# MSP430.net
KiCad netlist of a schematic drawn in Altium Designer
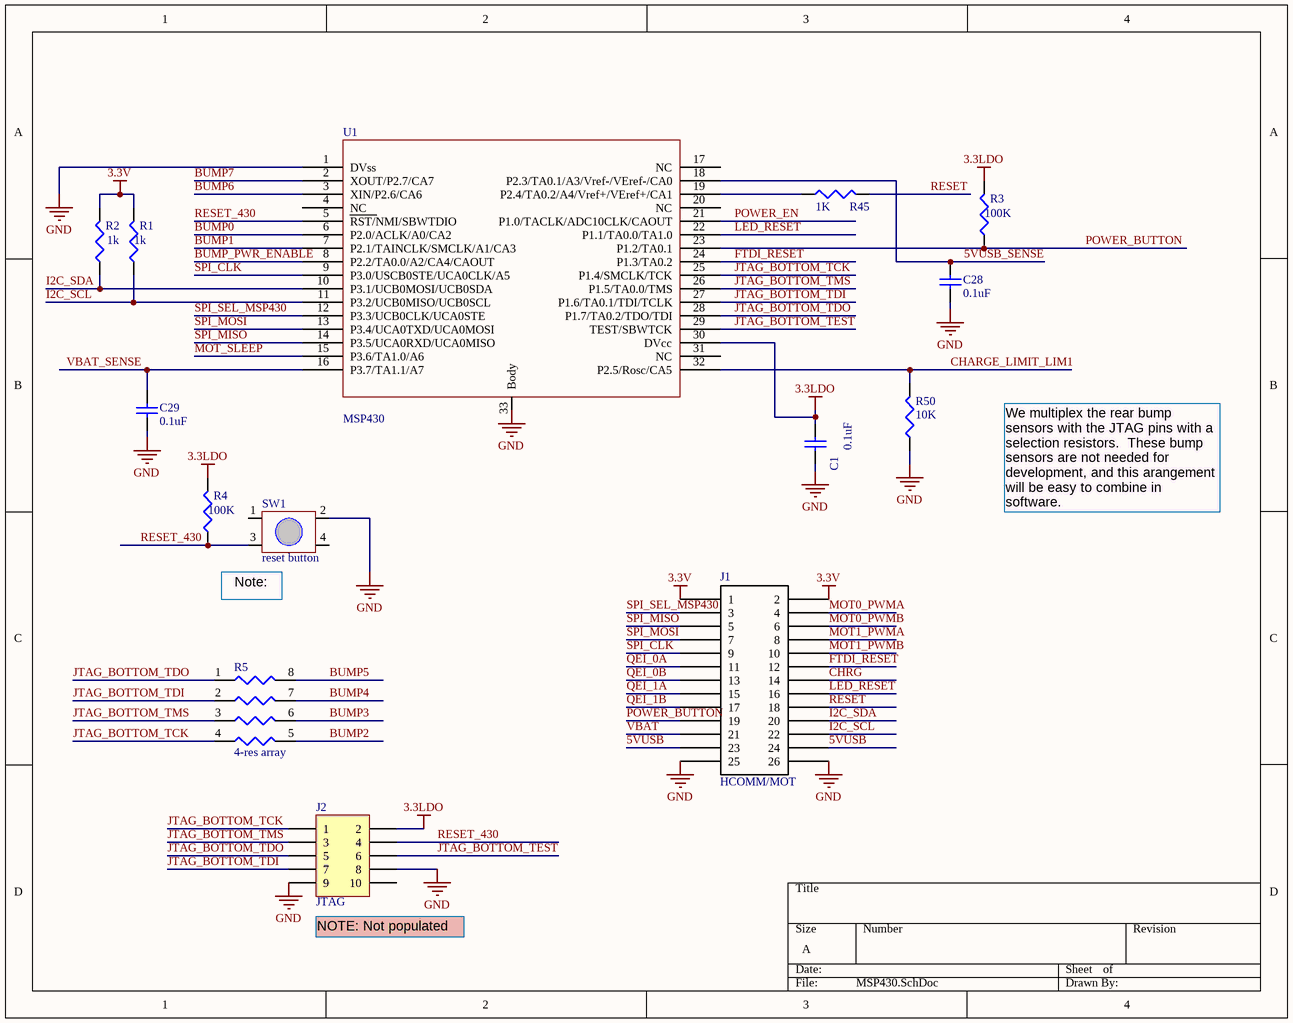
[diagram p0: MSP430.SchDoc]

(export (version "E")
  (design (tool "Eeschema 10.0.6"))
  (components
    (comp (ref "C1")
      (value "0.1uF")
      (footprint "CAPC1005L")
      (description "Capacitor (Semiconductor SIM Model)")
      (fields (field (name "Comment") "Cap Semi") (field (name "PUBLISHER") "Altium Limited"))
      (libsource (lib "Miscellaneous Devices") (part "Cap Semi"))
    )
    (comp (ref "C28")
      (value "0.1uF")
      (footprint "CAPC1005L")
      (description "Capacitor (Semiconductor SIM Model)")
      (fields (field (name "Comment") "Cap Semi") (field (name "PUBLISHER") "Altium Limited"))
      (libsource (lib "Miscellaneous Devices") (part "Cap Semi"))
    )
    (comp (ref "C29")
      (value "0.1uF")
      (footprint "CAPC1005L")
      (description "Capacitor (Semiconductor SIM Model)")
      (fields (field (name "Comment") "Cap Semi") (field (name "PUBLISHER") "Altium Limited"))
      (libsource (lib "Miscellaneous Devices") (part "Cap Semi"))
    )
    (comp (ref "J1")
      (value "HCOMM/MOT")
      (footprint "HeaderSM 13x2")
      (description "Header, 2X20, 50mil, IDC")
      (libsource (lib "mrone") (part "HCOMM/HMOT"))
    )
    (comp (ref "J2")
      (value "JTAG")
      (footprint "HDR2X5")
      (description "Header, 5-Pin, Dual row")
      (fields (field (name "PUBLISHER") "Altium Limited"))
      (libsource (lib "Miscellaneous Connectors") (part "Header 5X2"))
    )
    (comp (ref "R1")
      (value "1k")
      (footprint "RESC1608L")
      (description "Resistor")
      (fields (field (name "Comment") "Res3") (field (name "PUBLISHER") "Altium Limited"))
      (libsource (lib "Miscellaneous Devices") (part "Res3"))
    )
    (comp (ref "R2")
      (value "1k")
      (footprint "RESC1608L")
      (description "Resistor")
      (fields (field (name "Comment") "Res3") (field (name "PUBLISHER") "Altium Limited"))
      (libsource (lib "Miscellaneous Devices") (part "Res3"))
    )
    (comp (ref "R3")
      (value "100K")
      (footprint "RESC1608L")
      (description "Resistor")
      (fields (field (name "Comment") "Res3") (field (name "PUBLISHER") "Altium Limited"))
      (libsource (lib "Miscellaneous Devices") (part "Res3"))
    )
    (comp (ref "R4")
      (value "100K")
      (footprint "RESC1608L")
      (description "Resistor")
      (fields (field (name "Comment") "Res3") (field (name "PUBLISHER") "Altium Limited"))
      (libsource (lib "Miscellaneous Devices") (part "Res3"))
    )
    (comp (ref "R5")
      (value "4-res array")
      (footprint "4-RES ARRAY")
      (libsource (lib "mrone") (part "4 Res Array"))
    )
    (comp (ref "R45")
      (value "1K")
      (footprint "J1-0603")
      (description "Resistor")
      (fields (field (name "PUBLISHER") "Altium Limited"))
      (libsource (lib "Miscellaneous Devices") (part "Res3"))
    )
    (comp (ref "R50")
      (value "10K")
      (footprint "RESC1608L")
      (description "Resistor")
      (fields (field (name "Comment") "Res3") (field (name "PUBLISHER") "Altium Limited"))
      (libsource (lib "Miscellaneous Devices") (part "Res3"))
    )
    (comp (ref "SW1")
      (value "reset button")
      (footprint "SwitchTall-TL330")
      (libsource (lib "mrone") (part "Switch-TL330"))
    )
    (comp (ref "U1")
      (value "MSP430")
      (footprint "MSP430_32PIN")
      (libsource (lib "mrone") (part "MSP430_32pin"))
    )
  )
  (nets
    (net (code "1") (name "/5VUSB") (class "Default")
      (node (ref "J1") (pin "23") (pinfunction "23_23") (pintype "passive"))
      (node (ref "J1") (pin "24") (pinfunction "24_24") (pintype "passive"))
    )
    (net (code "2") (name "/5VUSB_SENSE") (class "Default")
      (node (ref "C28") (pin "2") (pinfunction "2_2") (pintype "passive"))
      (node (ref "U1") (pin "18") (pinfunction "P2.3/TA0.1/A3/Vref-/VEref-/CA0_18") (pintype "passive"))
    )
    (net (code "3") (name "/BUMP0") (class "Default")
      (node (ref "U1") (pin "6") (pinfunction "P2.0/ACLK/A0/CA2_6") (pintype "passive"))
    )
    (net (code "4") (name "/BUMP1") (class "Default")
      (node (ref "U1") (pin "7") (pinfunction "P2.1/TAINCLK/SMCLK/A1/CA3_7") (pintype "passive"))
    )
    (net (code "5") (name "/BUMP2") (class "Default")
      (node (ref "R5") (pin "5") (pinfunction "5_5") (pintype "passive"))
    )
    (net (code "6") (name "/BUMP3") (class "Default")
      (node (ref "R5") (pin "6") (pinfunction "6_6") (pintype "passive"))
    )
    (net (code "7") (name "/BUMP4") (class "Default")
      (node (ref "R5") (pin "7") (pinfunction "7_7") (pintype "passive"))
    )
    (net (code "8") (name "/BUMP5") (class "Default")
      (node (ref "R5") (pin "8") (pinfunction "8_8") (pintype "passive"))
    )
    (net (code "9") (name "/BUMP6") (class "Default")
      (node (ref "U1") (pin "3") (pinfunction "XIN/P2.6/CA6_3") (pintype "passive"))
    )
    (net (code "10") (name "/BUMP7") (class "Default")
      (node (ref "U1") (pin "2") (pinfunction "XOUT/P2.7/CA7_2") (pintype "passive"))
    )
    (net (code "11") (name "/BUMP_PWR_ENABLE") (class "Default")
      (node (ref "U1") (pin "8") (pinfunction "P2.2/TA0.0/A2/CA4/CAOUT_8") (pintype "passive"))
    )
    (net (code "12") (name "/CHARGE_LIMIT_LIM1") (class "Default")
      (node (ref "R50") (pin "2") (pinfunction "2_2") (pintype "passive"))
      (node (ref "U1") (pin "32") (pinfunction "P2.5/Rosc/CA5_32") (pintype "passive"))
    )
    (net (code "13") (name "/CHRG") (class "Default")
      (node (ref "J1") (pin "14") (pinfunction "14_14") (pintype "passive"))
    )
    (net (code "14") (name "/FTDI_RESET") (class "Default")
      (node (ref "J1") (pin "12") (pinfunction "12_12") (pintype "passive"))
      (node (ref "U1") (pin "24") (pinfunction "P1.3/TA0.2_24") (pintype "passive"))
    )
    (net (code "15") (name "/I2C_SCL") (class "Default")
      (node (ref "J1") (pin "22") (pinfunction "22_22") (pintype "passive"))
      (node (ref "R1") (pin "1") (pinfunction "1_1") (pintype "passive"))
      (node (ref "U1") (pin "11") (pinfunction "P3.2/UCB0MISO/UCB0SCL_11") (pintype "passive"))
    )
    (net (code "16") (name "/I2C_SDA") (class "Default")
      (node (ref "J1") (pin "20") (pinfunction "20_20") (pintype "passive"))
      (node (ref "R2") (pin "1") (pinfunction "1_1") (pintype "passive"))
      (node (ref "U1") (pin "10") (pinfunction "P3.1/UCB0MOSI/UCB0SDA_10") (pintype "passive"))
    )
    (net (code "17") (name "/JTAG_BOTTOM_TCK") (class "Default")
      (node (ref "J2") (pin "1") (pinfunction "1_1") (pintype "passive"))
      (node (ref "R5") (pin "4") (pinfunction "4_4") (pintype "passive"))
      (node (ref "U1") (pin "25") (pinfunction "P1.4/SMCLK/TCK_25") (pintype "passive"))
    )
    (net (code "18") (name "/JTAG_BOTTOM_TDI") (class "Default")
      (node (ref "J2") (pin "7") (pinfunction "7_7") (pintype "passive"))
      (node (ref "R5") (pin "2") (pinfunction "2_2") (pintype "passive"))
      (node (ref "U1") (pin "27") (pinfunction "P1.6/TA0.1/TDI/TCLK_27") (pintype "passive"))
    )
    (net (code "19") (name "/JTAG_BOTTOM_TDO") (class "Default")
      (node (ref "J2") (pin "5") (pinfunction "5_5") (pintype "passive"))
      (node (ref "R5") (pin "1") (pinfunction "1_1") (pintype "passive"))
      (node (ref "U1") (pin "28") (pinfunction "P1.7/TA0.2/TDO/TDI_28") (pintype "passive"))
    )
    (net (code "20") (name "/JTAG_BOTTOM_TEST") (class "Default")
      (node (ref "J2") (pin "6") (pinfunction "6_6") (pintype "passive"))
      (node (ref "U1") (pin "29") (pinfunction "TEST/SBWTCK_29") (pintype "passive"))
    )
    (net (code "21") (name "/JTAG_BOTTOM_TMS") (class "Default")
      (node (ref "J2") (pin "3") (pinfunction "3_3") (pintype "passive"))
      (node (ref "R5") (pin "3") (pinfunction "3_3") (pintype "passive"))
      (node (ref "U1") (pin "26") (pinfunction "P1.5/TA0.0/TMS_26") (pintype "passive"))
    )
    (net (code "22") (name "/LED_RESET") (class "Default")
      (node (ref "J1") (pin "16") (pinfunction "16_16") (pintype "passive"))
      (node (ref "U1") (pin "22") (pinfunction "P1.1/TA0.0/TA1.0_22") (pintype "passive"))
    )
    (net (code "23") (name "/MOT0_PWMA") (class "Default")
      (node (ref "J1") (pin "4") (pinfunction "4_4") (pintype "passive"))
    )
    (net (code "24") (name "/MOT0_PWMB") (class "Default")
      (node (ref "J1") (pin "6") (pinfunction "6_6") (pintype "passive"))
    )
    (net (code "25") (name "/MOT1_PWMA") (class "Default")
      (node (ref "J1") (pin "8") (pinfunction "8_8") (pintype "passive"))
    )
    (net (code "26") (name "/MOT1_PWMB") (class "Default")
      (node (ref "J1") (pin "10") (pinfunction "10_10") (pintype "passive"))
    )
    (net (code "27") (name "/MOT_SLEEP") (class "Default")
      (node (ref "U1") (pin "15") (pinfunction "P3.6/TA1.0/A6_15") (pintype "passive"))
    )
    (net (code "28") (name "/POWER_BUTTON") (class "Default")
      (node (ref "J1") (pin "19") (pinfunction "19_19") (pintype "passive"))
      (node (ref "R3") (pin "1") (pinfunction "1_1") (pintype "passive"))
      (node (ref "U1") (pin "23") (pinfunction "P1.2/TA0.1_23") (pintype "passive"))
    )
    (net (code "29") (name "/POWER_EN") (class "Default")
      (node (ref "U1") (pin "21") (pinfunction "P1.0/TACLK/ADC10CLK/CAOUT_21") (pintype "passive"))
    )
    (net (code "30") (name "/QEI_0A") (class "Default")
      (node (ref "J1") (pin "11") (pinfunction "11_11") (pintype "passive"))
    )
    (net (code "31") (name "/QEI_0B") (class "Default")
      (node (ref "J1") (pin "13") (pinfunction "13_13") (pintype "passive"))
    )
    (net (code "32") (name "/QEI_1A") (class "Default")
      (node (ref "J1") (pin "15") (pinfunction "15_15") (pintype "passive"))
    )
    (net (code "33") (name "/QEI_1B") (class "Default")
      (node (ref "J1") (pin "17") (pinfunction "17_17") (pintype "passive"))
    )
    (net (code "34") (name "/RESET") (class "Default")
      (node (ref "J1") (pin "18") (pinfunction "18_18") (pintype "passive"))
      (node (ref "R45") (pin "2") (pinfunction "2_2") (pintype "passive"))
    )
    (net (code "35") (name "/RESET_430") (class "Default")
      (node (ref "J2") (pin "4") (pinfunction "4_4") (pintype "passive"))
      (node (ref "R4") (pin "1") (pinfunction "1_1") (pintype "passive"))
      (node (ref "SW1") (pin "3") (pinfunction "3_3") (pintype "passive"))
      (node (ref "U1") (pin "5") (pinfunction "RST/NMI/SBWTDIO_5") (pintype "passive"))
    )
    (net (code "36") (name "/SPI_CLK") (class "Default")
      (node (ref "J1") (pin "9") (pinfunction "9_9") (pintype "passive"))
      (node (ref "U1") (pin "9") (pinfunction "P3.0/USCB0STE/UCA0CLK/A5_9") (pintype "passive"))
    )
    (net (code "37") (name "/SPI_MISO") (class "Default")
      (node (ref "J1") (pin "5") (pinfunction "5_5") (pintype "passive"))
      (node (ref "U1") (pin "14") (pinfunction "P3.5/UCA0RXD/UCA0MISO_14") (pintype "passive"))
    )
    (net (code "38") (name "/SPI_MOSI") (class "Default")
      (node (ref "J1") (pin "7") (pinfunction "7_7") (pintype "passive"))
      (node (ref "U1") (pin "13") (pinfunction "P3.4/UCA0TXD/UCA0MOSI_13") (pintype "passive"))
    )
    (net (code "39") (name "/SPI_SEL_MSP430") (class "Default")
      (node (ref "J1") (pin "3") (pinfunction "3_3") (pintype "passive"))
      (node (ref "U1") (pin "12") (pinfunction "P3.3/UCB0CLK/UCA0STE_12") (pintype "passive"))
    )
    (net (code "40") (name "/VBAT") (class "Default")
      (node (ref "J1") (pin "21") (pinfunction "21_21") (pintype "passive"))
    )
    (net (code "41") (name "/VBAT_SENSE") (class "Default")
      (node (ref "C29") (pin "2") (pinfunction "2_2") (pintype "passive"))
      (node (ref "U1") (pin "16") (pinfunction "P3.7/TA1.1/A7_16") (pintype "passive"))
    )
    (net (code "42") (name "3.3LDO") (class "Default")
      (node (ref "C1") (pin "2") (pinfunction "2_2") (pintype "passive"))
      (node (ref "J2") (pin "2") (pinfunction "2_2") (pintype "passive"))
      (node (ref "R3") (pin "2") (pinfunction "2_2") (pintype "passive"))
      (node (ref "R4") (pin "2") (pinfunction "2_2") (pintype "passive"))
      (node (ref "U1") (pin "30") (pinfunction "DVcc_30") (pintype "passive"))
    )
    (net (code "43") (name "3.3V") (class "Default")
      (node (ref "J1") (pin "1") (pinfunction "1_1") (pintype "passive"))
      (node (ref "J1") (pin "2") (pinfunction "2_2") (pintype "passive"))
      (node (ref "R1") (pin "2") (pinfunction "2_2") (pintype "passive"))
      (node (ref "R2") (pin "2") (pinfunction "2_2") (pintype "passive"))
    )
    (net (code "44") (name "GND") (class "Default")
      (node (ref "C1") (pin "1") (pinfunction "1_1") (pintype "passive"))
      (node (ref "C28") (pin "1") (pinfunction "1_1") (pintype "passive"))
      (node (ref "C29") (pin "1") (pinfunction "1_1") (pintype "passive"))
      (node (ref "J1") (pin "25") (pinfunction "25_25") (pintype "passive"))
      (node (ref "J1") (pin "26") (pinfunction "26_26") (pintype "passive"))
      (node (ref "J2") (pin "8") (pinfunction "8_8") (pintype "passive"))
      (node (ref "J2") (pin "9") (pinfunction "9_9") (pintype "passive"))
      (node (ref "R50") (pin "1") (pinfunction "1_1") (pintype "passive"))
      (node (ref "SW1") (pin "2") (pinfunction "2_2") (pintype "passive"))
      (node (ref "U1") (pin "1") (pinfunction "DVss_1") (pintype "passive"))
      (node (ref "U1") (pin "33") (pinfunction "Body_33") (pintype "power_in"))
    )
    (net (code "45") (name "Net-(U1-P2.4{slash}TA0.2{slash}A4{slash}Vref+{slash}VEref+{slash}CA1)") (class "Default")
      (node (ref "R45") (pin "1") (pinfunction "1_1") (pintype "passive"))
      (node (ref "U1") (pin "19") (pinfunction "P2.4/TA0.2/A4/Vref+/VEref+/CA1_19") (pintype "passive"))
    )
    (net (code "46") (name "unconnected-(J2-Pad10)") (class "Default")
      (node (ref "J2") (pin "10") (pinfunction "10_10") (pintype "passive"))
    )
    (net (code "47") (name "unconnected-(SW1-Pad1)") (class "Default")
      (node (ref "SW1") (pin "1") (pinfunction "1_1") (pintype "passive"))
    )
    (net (code "48") (name "unconnected-(SW1-Pad4)") (class "Default")
      (node (ref "SW1") (pin "4") (pinfunction "4_4") (pintype "passive"))
    )
    (net (code "49") (name "unconnected-(U1-NC-Pad4)") (class "Default")
      (node (ref "U1") (pin "4") (pinfunction "NC_4") (pintype "passive"))
    )
    (net (code "50") (name "unconnected-(U1-NC-Pad17)") (class "Default")
      (node (ref "U1") (pin "17") (pinfunction "NC_17") (pintype "passive"))
    )
    (net (code "51") (name "unconnected-(U1-NC-Pad20)") (class "Default")
      (node (ref "U1") (pin "20") (pinfunction "NC_20") (pintype "passive"))
    )
    (net (code "52") (name "unconnected-(U1-NC-Pad31)") (class "Default")
      (node (ref "U1") (pin "31") (pinfunction "NC_31") (pintype "passive"))
    )
  )
)
